# ETH_M_V1.net
KiCad netlist of a schematic drawn in Altium Designer
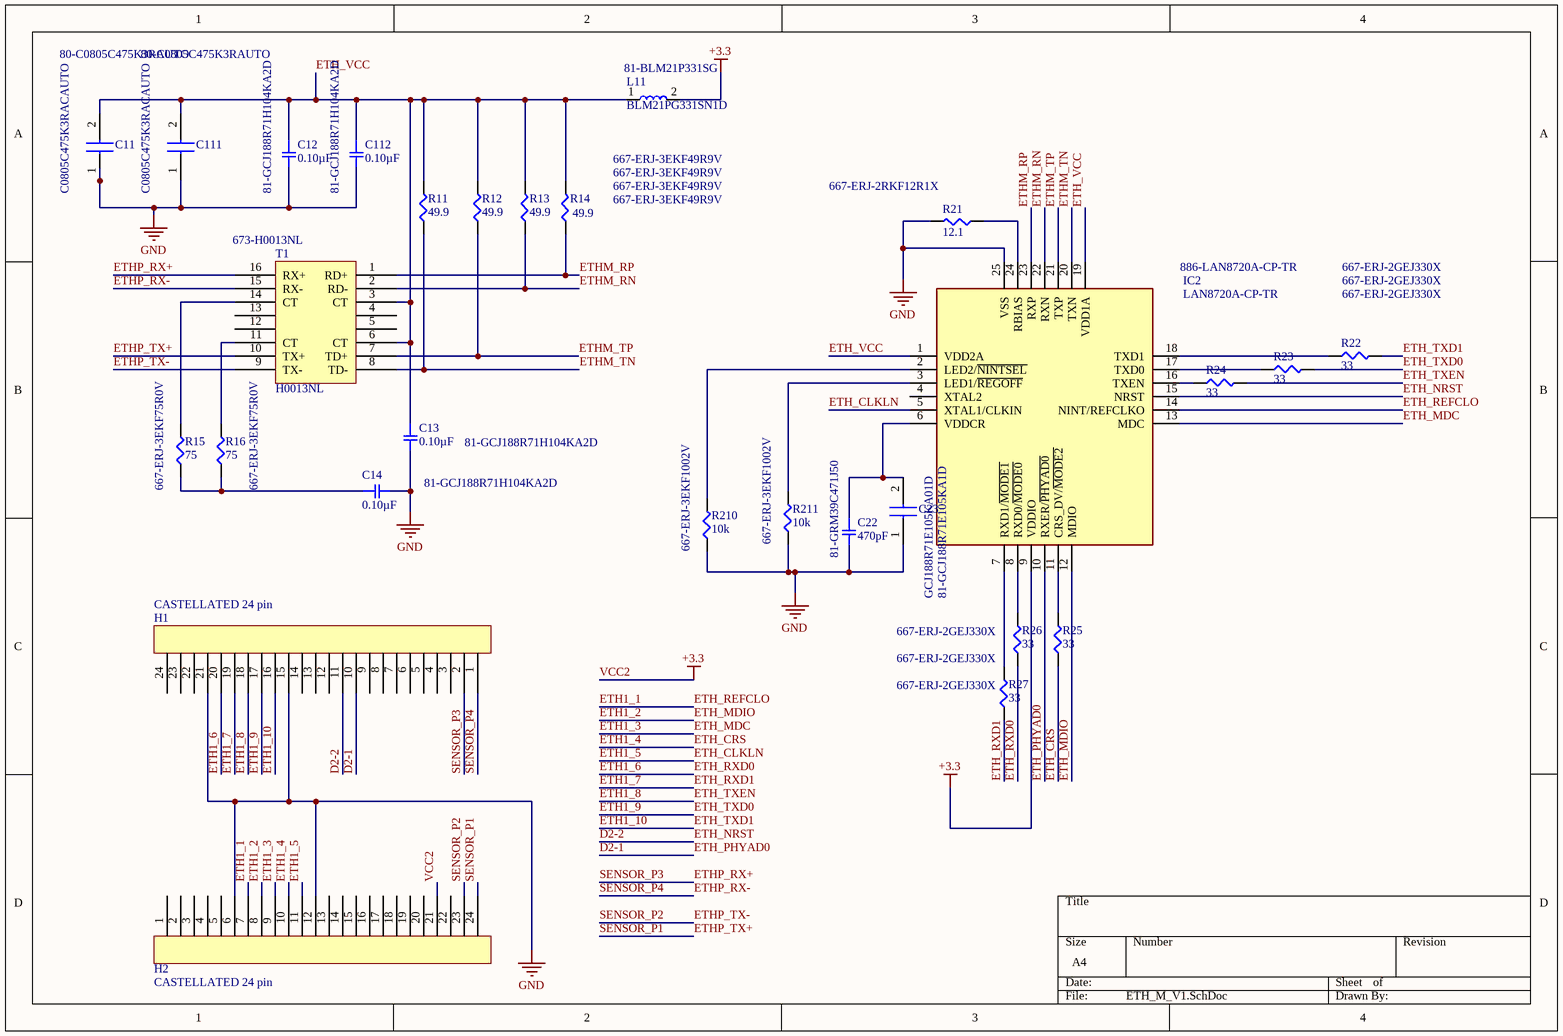
[diagram p0: ETH_M_V1.SchDoc]

(export (version "E")
  (design (tool "Eeschema 10.0.6"))
  (components
    (comp (ref "C11")
      (value "C0805C475K3RACAUTO")
      (footprint "SamacSys:CAPC2012X125N")
      (description "Capacitor")
      (fields
        (field (name "MOUSER2 PART NUMBER") "80-C0805C475K3RAUTO")
        (field (name "SUPPLIER PART NUMBER 1") "80-C0805C475K3RAUTO")
      )
      (libsource (lib "*") (part "C0805C475K3RACAUTO"))
    )
    (comp (ref "C12")
      (value "0.10µF")
      (footprint "SMD-0603C")
      (description "CAP CER 0.1UF 50V X7R 0603")
      (fields
        (field (name "DIGI-KEY PART NUMBER") "490-5798-1-ND")
        (field (name "PART NUMBER") "GCJ188R71H104KA12D")
        (field (name "SUPPLIER PART NUMBER 1") "81-GCJ188R71H104KA2D")
      )
      (libsource (lib "capacitor_murata_0603") (part "GCJ188R71H104KA12D"))
    )
    (comp (ref "C13")
      (value "0.10µF")
      (footprint "SMD-0603C")
      (description "CAP CER 0.1UF 50V X7R 0603")
      (fields
        (field (name "DIGI-KEY PART NUMBER") "490-5798-1-ND")
        (field (name "PART NUMBER") "GCJ188R71H104KA12D")
        (field (name "SUPPLIER PART NUMBER 1") "81-GCJ188R71H104KA2D")
      )
      (libsource (lib "capacitor_murata_0603") (part "GCJ188R71H104KA12D"))
    )
    (comp (ref "C14")
      (value "0.10µF")
      (footprint "SMD-0603C")
      (description "CAP CER 0.1UF 50V X7R 0603")
      (fields
        (field (name "DIGI-KEY PART NUMBER") "490-5798-1-ND")
        (field (name "PART NUMBER") "GCJ188R71H104KA12D")
        (field (name "SUPPLIER PART NUMBER 1") "81-GCJ188R71H104KA2D")
      )
      (libsource (lib "capacitor_murata_0603") (part "GCJ188R71H104KA12D"))
    )
    (comp (ref "C22")
      (value "470pF")
      (footprint "SMD-0603C")
      (description "CAP CER 470PF 50V NP0 0603")
      (fields
        (field (name "DIGI-KEY PART NUMBER") "490-1443-1-ND")
        (field (name "PART NUMBER") "GRM1885C1H471JA01D")
        (field (name "SUPPLIER PART NUMBER 1") "81-GRM39C471J50")
      )
      (libsource (lib "capacitor_murata_0603") (part "GRM1885C1H471JA01D"))
    )
    (comp (ref "C23")
      (value "GCJ188R71E105KA01D")
      (footprint "SamacSys:CAPC1608X100N")
      (description "Capacitor")
      (fields (field (name "SUPPLIER PART NUMBER 1") "81-GCJ188R71E105KA1D"))
      (libsource (lib "*") (part "GCJ188R71E105KA01D"))
    )
    (comp (ref "C111")
      (value "C0805C475K3RACAUTO")
      (footprint "SamacSys:CAPC2012X125N")
      (description "Capacitor")
      (fields
        (field (name "MOUSER2 PART NUMBER") "80-C0805C475K3RAUTO")
        (field (name "SUPPLIER PART NUMBER 1") "80-C0805C475K3RAUTO")
      )
      (libsource (lib "*") (part "C0805C475K3RACAUTO"))
    )
    (comp (ref "C112")
      (value "0.10µF")
      (footprint "SMD-0603C")
      (description "CAP CER 0.1UF 50V X7R 0603")
      (fields
        (field (name "DIGI-KEY PART NUMBER") "490-5798-1-ND")
        (field (name "PART NUMBER") "GCJ188R71H104KA12D")
        (field (name "SUPPLIER PART NUMBER 1") "81-GCJ188R71H104KA2D")
      )
      (libsource (lib "capacitor_murata_0603") (part "GCJ188R71H104KA12D"))
    )
    (comp (ref "H1")
      (value "CASTELLATED 24 pin")
      (footprint "CASTELLATED 24 pin")
      (libsource (lib "") (part "CASTELLATED 24 pin_1"))
    )
    (comp (ref "H2")
      (value "CASTELLATED 24 pin")
      (footprint "CASTELLATED 24 pin")
      (libsource (lib "USIB") (part "CASTELLATED 24 pin"))
    )
    (comp (ref "IC2")
      (value "LAN8720A-CP-TR")
      (footprint "SamacSys:QFN50P400X400X100-25N-D")
      (description "Integrated Circuit")
      (fields
        (field (name "MOUSER2 PART NUMBER") "886-LAN8720A-CP-TR")
        (field (name "SUPPLIER PART NUMBER 1") "886-LAN8720A-CP-TR")
      )
      (libsource (lib "*") (part "LAN8720A-CP-TR"))
    )
    (comp (ref "L11")
      (value "BLM21PG331SN1D")
      (footprint "INDC2012X87")
      (description "Ferrite Beads Multi-Layer 330Ohm 25% 100MHz 1.5A 70mOhm DCR 0805 Paper T/R")
      (fields
        (field (name "MF") "Murata")
        (field (name "DIGI-KEY_PART_NUMBER") "490-5988-1-ND")
        (field (name "SUPPLIER PART NUMBER 1") "81-BLM21P331SG")
      )
      (libsource (lib "BLM21PG331SN1D") (part "BLM21PG331SN1D"))
    )
    (comp (ref "R11")
      (value "49.9")
      (footprint "SMD-0603-RES")
      (description "RES SMD 49.9 OHM 1% 1/10W 0603")
      (fields
        (field (name "PART NUMBER") "ERJ-3EKF49R9V")
        (field (name "DIGI-KEY PART NUMBER") "P49.9HCT-ND")
        (field (name "SUPPLIER PART NUMBER 1") "667-ERJ-3EKF49R9V")
      )
      (libsource (lib "Panasonic_ERJ_0603") (part "ERJ-3EKF49R9V"))
    )
    (comp (ref "R12")
      (value "49.9")
      (footprint "SMD-0603-RES")
      (description "RES SMD 49.9 OHM 1% 1/10W 0603")
      (fields
        (field (name "PART NUMBER") "ERJ-3EKF49R9V")
        (field (name "DIGI-KEY PART NUMBER") "P49.9HCT-ND")
        (field (name "SUPPLIER PART NUMBER 1") "667-ERJ-3EKF49R9V")
      )
      (libsource (lib "Panasonic_ERJ_0603") (part "ERJ-3EKF49R9V"))
    )
    (comp (ref "R13")
      (value "49.9")
      (footprint "SMD-0603-RES")
      (description "RES SMD 49.9 OHM 1% 1/10W 0603")
      (fields
        (field (name "PART NUMBER") "ERJ-3EKF49R9V")
        (field (name "DIGI-KEY PART NUMBER") "P49.9HCT-ND")
        (field (name "SUPPLIER PART NUMBER 1") "667-ERJ-3EKF49R9V")
      )
      (libsource (lib "Panasonic_ERJ_0603") (part "ERJ-3EKF49R9V"))
    )
    (comp (ref "R14")
      (value "49.9")
      (footprint "SMD-0603-RES")
      (description "RES SMD 49.9 OHM 1% 1/10W 0603")
      (fields
        (field (name "PART NUMBER") "ERJ-3EKF49R9V")
        (field (name "DIGI-KEY PART NUMBER") "P49.9HCT-ND")
        (field (name "SUPPLIER PART NUMBER 1") "667-ERJ-3EKF49R9V")
      )
      (libsource (lib "Panasonic_ERJ_0603") (part "ERJ-3EKF49R9V"))
    )
    (comp (ref "R15")
      (value "75")
      (footprint "SMD-0603-RES")
      (description "RES SMD 75 OHM 1% 1/10W 0603")
      (fields
        (field (name "PART NUMBER") "ERJ-3EKF75R0V")
        (field (name "DIGI-KEY PART NUMBER") "P75.0HCT-ND")
        (field (name "SUPPLIER PART NUMBER 1") "667-ERJ-3EKF75R0V")
      )
      (libsource (lib "Panasonic_ERJ_0603") (part "ERJ-3EKF75R0V"))
    )
    (comp (ref "R16")
      (value "75")
      (footprint "SMD-0603-RES")
      (description "RES SMD 75 OHM 1% 1/10W 0603")
      (fields
        (field (name "PART NUMBER") "ERJ-3EKF75R0V")
        (field (name "DIGI-KEY PART NUMBER") "P75.0HCT-ND")
        (field (name "SUPPLIER PART NUMBER 1") "667-ERJ-3EKF75R0V")
      )
      (libsource (lib "Panasonic_ERJ_0603") (part "ERJ-3EKF75R0V"))
    )
    (comp (ref "R21")
      (value "12.1")
      (footprint "SMD-0402-RES")
      (description "RES SMD 12.1 OHM 1% 1/10W 0402")
      (fields
        (field (name "PART NUMBER") "ERJ-2RKF12R1X")
        (field (name "DIGI-KEY PART NUMBER") "P12.1LCT-ND")
        (field (name "SUPPLIER PART NUMBER 1") "667-ERJ-2RKF12R1X")
      )
      (libsource (lib "Panasonic_ERJ_0402") (part "ERJ-2RKF12R1X"))
    )
    (comp (ref "R22")
      (value "33")
      (footprint "SMD-0402-RES")
      (description "RES SMD 33 OHM 5% 1/10W 0402")
      (fields
        (field (name "PART NUMBER") "ERJ-2GEJ330X")
        (field (name "DIGI-KEY PART NUMBER") "P33JCT-ND")
        (field (name "SUPPLIER PART NUMBER 1") "667-ERJ-2GEJ330X")
      )
      (libsource (lib "Panasonic_ERJ_0402") (part "ERJ-2GEJ330X"))
    )
    (comp (ref "R23")
      (value "33")
      (footprint "SMD-0402-RES")
      (description "RES SMD 33 OHM 5% 1/10W 0402")
      (fields
        (field (name "PART NUMBER") "ERJ-2GEJ330X")
        (field (name "DIGI-KEY PART NUMBER") "P33JCT-ND")
        (field (name "SUPPLIER PART NUMBER 1") "667-ERJ-2GEJ330X")
      )
      (libsource (lib "Panasonic_ERJ_0402") (part "ERJ-2GEJ330X"))
    )
    (comp (ref "R24")
      (value "33")
      (footprint "SMD-0402-RES")
      (description "RES SMD 33 OHM 5% 1/10W 0402")
      (fields
        (field (name "PART NUMBER") "ERJ-2GEJ330X")
        (field (name "DIGI-KEY PART NUMBER") "P33JCT-ND")
        (field (name "SUPPLIER PART NUMBER 1") "667-ERJ-2GEJ330X")
      )
      (libsource (lib "Panasonic_ERJ_0402") (part "ERJ-2GEJ330X"))
    )
    (comp (ref "R25")
      (value "33")
      (footprint "SMD-0402-RES")
      (description "RES SMD 33 OHM 5% 1/10W 0402")
      (fields
        (field (name "PART NUMBER") "ERJ-2GEJ330X")
        (field (name "DIGI-KEY PART NUMBER") "P33JCT-ND")
        (field (name "SUPPLIER PART NUMBER 1") "667-ERJ-2GEJ330X")
      )
      (libsource (lib "Panasonic_ERJ_0402") (part "ERJ-2GEJ330X"))
    )
    (comp (ref "R26")
      (value "33")
      (footprint "SMD-0402-RES")
      (description "RES SMD 33 OHM 5% 1/10W 0402")
      (fields
        (field (name "PART NUMBER") "ERJ-2GEJ330X")
        (field (name "DIGI-KEY PART NUMBER") "P33JCT-ND")
        (field (name "SUPPLIER PART NUMBER 1") "667-ERJ-2GEJ330X")
      )
      (libsource (lib "Panasonic_ERJ_0402") (part "ERJ-2GEJ330X"))
    )
    (comp (ref "R27")
      (value "33")
      (footprint "SMD-0402-RES")
      (description "RES SMD 33 OHM 5% 1/10W 0402")
      (fields
        (field (name "PART NUMBER") "ERJ-2GEJ330X")
        (field (name "DIGI-KEY PART NUMBER") "P33JCT-ND")
        (field (name "SUPPLIER PART NUMBER 1") "667-ERJ-2GEJ330X")
      )
      (libsource (lib "Panasonic_ERJ_0402") (part "ERJ-2GEJ330X"))
    )
    (comp (ref "R210")
      (value "10k")
      (footprint "SMD-0603-RES")
      (description "RES SMD 10K OHM 1% 1/10W 0603")
      (fields
        (field (name "PART NUMBER") "ERJ-3EKF1002V")
        (field (name "DIGI-KEY PART NUMBER") "P10.0KHCT-ND")
        (field (name "SUPPLIER PART NUMBER 1") "667-ERJ-3EKF1002V")
      )
      (libsource (lib "Panasonic_ERJ_0603") (part "ERJ-3EKF1002V"))
    )
    (comp (ref "R211")
      (value "10k")
      (footprint "SMD-0603-RES")
      (description "RES SMD 10K OHM 1% 1/10W 0603")
      (fields
        (field (name "PART NUMBER") "ERJ-3EKF1002V")
        (field (name "DIGI-KEY PART NUMBER") "P10.0KHCT-ND")
        (field (name "SUPPLIER PART NUMBER 1") "667-ERJ-3EKF1002V")
      )
      (libsource (lib "Panasonic_ERJ_0603") (part "ERJ-3EKF1002V"))
    )
    (comp (ref "T1")
      (value "H0013NL")
      (footprint "SamacSys:H0013NL")
      (description "Transformer")
      (fields (field (name "SUPPLIER PART NUMBER 1") "673-H0013NL"))
      (libsource (lib "SamacSys") (part "H0013NL"))
    )
  )
  (nets
    (net (code "1") (name "+3.3") (class "Default")
      (node (ref "H2") (pin "21") (pintype "passive"))
      (node (ref "IC2") (pin "9") (pinfunction "VDDIO_9") (pintype "passive"))
      (node (ref "L11") (pin "2") (pinfunction "2_2") (pintype "passive"))
    )
    (net (code "2") (name "/D2-1") (class "Default")
      (node (ref "H1") (pin "10") (pintype "passive"))
      (node (ref "IC2") (pin "10") (pinfunction "RXER/~{PHYAD0}_10") (pintype "passive"))
    )
    (net (code "3") (name "/D2-2") (class "Default")
      (node (ref "H1") (pin "11") (pintype "passive"))
      (node (ref "IC2") (pin "15") (pinfunction "NRST_15") (pintype "passive"))
    )
    (net (code "4") (name "/ETH1_1") (class "Default")
      (node (ref "H2") (pin "7") (pintype "passive"))
      (node (ref "IC2") (pin "14") (pinfunction "NINT/REFCLKO_14") (pintype "passive"))
    )
    (net (code "5") (name "/ETH1_2") (class "Default")
      (node (ref "H2") (pin "8") (pintype "passive"))
      (node (ref "IC2") (pin "12") (pinfunction "MDIO_12") (pintype "passive"))
    )
    (net (code "6") (name "/ETH1_3") (class "Default")
      (node (ref "H2") (pin "9") (pintype "passive"))
      (node (ref "IC2") (pin "13") (pinfunction "MDC_13") (pintype "passive"))
    )
    (net (code "7") (name "/ETH1_4") (class "Default")
      (node (ref "H2") (pin "10") (pintype "passive"))
      (node (ref "R25") (pin "1") (pinfunction "1_1") (pintype "passive"))
    )
    (net (code "8") (name "/ETH1_5") (class "Default")
      (node (ref "H2") (pin "11") (pintype "passive"))
      (node (ref "IC2") (pin "5") (pinfunction "XTAL1/CLKIN_5") (pintype "passive"))
    )
    (net (code "9") (name "/ETH1_6") (class "Default")
      (node (ref "H1") (pin "20") (pintype "passive"))
      (node (ref "R26") (pin "1") (pinfunction "1_1") (pintype "passive"))
    )
    (net (code "10") (name "/ETH1_7") (class "Default")
      (node (ref "H1") (pin "19") (pintype "passive"))
      (node (ref "R27") (pin "1") (pinfunction "1_1") (pintype "passive"))
    )
    (net (code "11") (name "/ETH1_8") (class "Default")
      (node (ref "H1") (pin "18") (pintype "passive"))
      (node (ref "R24") (pin "2") (pinfunction "2_2") (pintype "passive"))
    )
    (net (code "12") (name "/ETH1_9") (class "Default")
      (node (ref "H1") (pin "17") (pintype "passive"))
      (node (ref "R23") (pin "2") (pinfunction "2_2") (pintype "passive"))
    )
    (net (code "13") (name "/ETH1_10") (class "Default")
      (node (ref "H1") (pin "16") (pintype "passive"))
      (node (ref "R22") (pin "2") (pinfunction "2_2") (pintype "passive"))
    )
    (net (code "14") (name "/ETHM_RN") (class "Default")
      (node (ref "IC2") (pin "22") (pinfunction "RXN_22") (pintype "passive"))
      (node (ref "R13") (pin "1") (pinfunction "1_1") (pintype "passive"))
      (node (ref "T1") (pin "2") (pinfunction "RD-_2") (pintype "passive"))
    )
    (net (code "15") (name "/ETHM_RP") (class "Default")
      (node (ref "IC2") (pin "23") (pinfunction "RXP_23") (pintype "passive"))
      (node (ref "R14") (pin "1") (pinfunction "1_1") (pintype "passive"))
      (node (ref "T1") (pin "1") (pinfunction "RD+_1") (pintype "passive"))
    )
    (net (code "16") (name "/ETHM_TN") (class "Default")
      (node (ref "IC2") (pin "20") (pinfunction "TXN_20") (pintype "passive"))
      (node (ref "R11") (pin "1") (pinfunction "1_1") (pintype "passive"))
      (node (ref "T1") (pin "8") (pinfunction "TD-_8") (pintype "passive"))
    )
    (net (code "17") (name "/ETHM_TP") (class "Default")
      (node (ref "IC2") (pin "21") (pinfunction "TXP_21") (pintype "passive"))
      (node (ref "R12") (pin "1") (pinfunction "1_1") (pintype "passive"))
      (node (ref "T1") (pin "7") (pinfunction "TD+_7") (pintype "passive"))
    )
    (net (code "18") (name "/ETHP_RX+") (class "Default")
      (node (ref "H1") (pin "2") (pintype "passive"))
      (node (ref "T1") (pin "16") (pinfunction "RX+_16") (pintype "passive"))
    )
    (net (code "19") (name "/ETHP_RX-") (class "Default")
      (node (ref "H1") (pin "1") (pintype "passive"))
      (node (ref "T1") (pin "15") (pinfunction "RX-_15") (pintype "passive"))
    )
    (net (code "20") (name "/ETHP_TX+") (class "Default")
      (node (ref "H2") (pin "24") (pintype "passive"))
      (node (ref "T1") (pin "10") (pinfunction "TX+_10") (pintype "passive"))
    )
    (net (code "21") (name "/ETHP_TX-") (class "Default")
      (node (ref "H2") (pin "23") (pintype "passive"))
      (node (ref "T1") (pin "9") (pinfunction "TX-_9") (pintype "passive"))
    )
    (net (code "22") (name "/ETH_VCC") (class "Default")
      (node (ref "C11") (pin "2") (pinfunction "2_2") (pintype "passive"))
      (node (ref "C111") (pin "2") (pinfunction "2_2") (pintype "passive"))
      (node (ref "C112") (pin "1") (pinfunction "1_1") (pintype "passive"))
      (node (ref "C12") (pin "1") (pinfunction "1_1") (pintype "passive"))
      (node (ref "C13") (pin "1") (pinfunction "1_1") (pintype "passive"))
      (node (ref "IC2") (pin "1") (pinfunction "VDD2A_1") (pintype "passive"))
      (node (ref "IC2") (pin "19") (pinfunction "VDD1A_19") (pintype "passive"))
      (node (ref "L11") (pin "1") (pinfunction "1_1") (pintype "passive"))
      (node (ref "R11") (pin "2") (pinfunction "2_2") (pintype "passive"))
      (node (ref "R12") (pin "2") (pinfunction "2_2") (pintype "passive"))
      (node (ref "R13") (pin "2") (pinfunction "2_2") (pintype "passive"))
      (node (ref "R14") (pin "2") (pinfunction "2_2") (pintype "passive"))
      (node (ref "T1") (pin "3") (pinfunction "CT_3") (pintype "passive"))
      (node (ref "T1") (pin "6") (pinfunction "CT_6") (pintype "passive"))
    )
    (net (code "23") (name "GND") (class "Default")
      (node (ref "C11") (pin "1") (pinfunction "1_1") (pintype "passive"))
      (node (ref "C111") (pin "1") (pinfunction "1_1") (pintype "passive"))
      (node (ref "C112") (pin "2") (pinfunction "2_2") (pintype "passive"))
      (node (ref "C12") (pin "2") (pinfunction "2_2") (pintype "passive"))
      (node (ref "C13") (pin "2") (pinfunction "2_2") (pintype "passive"))
      (node (ref "C14") (pin "2") (pinfunction "2_2") (pintype "passive"))
      (node (ref "C22") (pin "2") (pinfunction "2_2") (pintype "passive"))
      (node (ref "C23") (pin "1") (pinfunction "1_1") (pintype "passive"))
      (node (ref "H1") (pin "15") (pintype "passive"))
      (node (ref "H1") (pin "21") (pintype "passive"))
      (node (ref "H2") (pin "12") (pintype "passive"))
      (node (ref "H2") (pin "6") (pintype "passive"))
      (node (ref "IC2") (pin "25") (pinfunction "VSS_25") (pintype "passive"))
      (node (ref "R21") (pin "2") (pinfunction "2_2") (pintype "passive"))
      (node (ref "R210") (pin "1") (pinfunction "1_1") (pintype "passive"))
      (node (ref "R211") (pin "1") (pinfunction "1_1") (pintype "passive"))
    )
    (net (code "24") (name "Net-(C14-Pad1)") (class "Default")
      (node (ref "C14") (pin "1") (pinfunction "1_1") (pintype "passive"))
      (node (ref "R15") (pin "1") (pinfunction "1_1") (pintype "passive"))
      (node (ref "R16") (pin "1") (pinfunction "1_1") (pintype "passive"))
    )
    (net (code "25") (name "Net-(IC2-CRS_DV{slash}~{MODE2})") (class "Default")
      (node (ref "IC2") (pin "11") (pinfunction "CRS_DV/~{MODE2}_11") (pintype "passive"))
      (node (ref "R25") (pin "2") (pinfunction "2_2") (pintype "passive"))
    )
    (net (code "26") (name "Net-(IC2-LED1{slash}~{REGOFF})") (class "Default")
      (node (ref "IC2") (pin "3") (pinfunction "LED1/~{REGOFF}_3") (pintype "passive"))
      (node (ref "R211") (pin "2") (pinfunction "2_2") (pintype "passive"))
    )
    (net (code "27") (name "Net-(IC2-LED2{slash}~{NINTSEL})") (class "Default")
      (node (ref "IC2") (pin "2") (pinfunction "LED2/~{NINTSEL}_2") (pintype "passive"))
      (node (ref "R210") (pin "2") (pinfunction "2_2") (pintype "passive"))
    )
    (net (code "28") (name "Net-(IC2-RBIAS)") (class "Default")
      (node (ref "IC2") (pin "24") (pinfunction "RBIAS_24") (pintype "passive"))
      (node (ref "R21") (pin "1") (pinfunction "1_1") (pintype "passive"))
    )
    (net (code "29") (name "Net-(IC2-RXD0{slash}~{MODE0})") (class "Default")
      (node (ref "IC2") (pin "8") (pinfunction "RXD0/~{MODE0}_8") (pintype "passive"))
      (node (ref "R26") (pin "2") (pinfunction "2_2") (pintype "passive"))
    )
    (net (code "30") (name "Net-(IC2-RXD1{slash}~{MODE1})") (class "Default")
      (node (ref "IC2") (pin "7") (pinfunction "RXD1/~{MODE1}_7") (pintype "passive"))
      (node (ref "R27") (pin "2") (pinfunction "2_2") (pintype "passive"))
    )
    (net (code "31") (name "Net-(IC2-TXD0)") (class "Default")
      (node (ref "IC2") (pin "17") (pinfunction "TXD0_17") (pintype "passive"))
      (node (ref "R23") (pin "1") (pinfunction "1_1") (pintype "passive"))
    )
    (net (code "32") (name "Net-(IC2-TXD1)") (class "Default")
      (node (ref "IC2") (pin "18") (pinfunction "TXD1_18") (pintype "passive"))
      (node (ref "R22") (pin "1") (pinfunction "1_1") (pintype "passive"))
    )
    (net (code "33") (name "Net-(IC2-TXEN)") (class "Default")
      (node (ref "IC2") (pin "16") (pinfunction "TXEN_16") (pintype "passive"))
      (node (ref "R24") (pin "1") (pinfunction "1_1") (pintype "passive"))
    )
    (net (code "34") (name "Net-(IC2-VDDCR)") (class "Default")
      (node (ref "C22") (pin "1") (pinfunction "1_1") (pintype "passive"))
      (node (ref "C23") (pin "2") (pinfunction "2_2") (pintype "passive"))
      (node (ref "IC2") (pin "6") (pinfunction "VDDCR_6") (pintype "passive"))
    )
    (net (code "35") (name "Net-(R15-Pad2)") (class "Default")
      (node (ref "R15") (pin "2") (pinfunction "2_2") (pintype "passive"))
      (node (ref "T1") (pin "14") (pinfunction "CT_14") (pintype "passive"))
    )
    (net (code "36") (name "Net-(R16-Pad2)") (class "Default")
      (node (ref "R16") (pin "2") (pinfunction "2_2") (pintype "passive"))
      (node (ref "T1") (pin "11") (pinfunction "CT_11") (pintype "passive"))
    )
    (net (code "37") (name "unconnected-(H1-Pad3)") (class "Default")
      (node (ref "H1") (pin "3") (pintype "passive"))
    )
    (net (code "38") (name "unconnected-(H1-Pad4)") (class "Default")
      (node (ref "H1") (pin "4") (pintype "passive"))
    )
    (net (code "39") (name "unconnected-(H1-Pad5)") (class "Default")
      (node (ref "H1") (pin "5") (pintype "passive"))
    )
    (net (code "40") (name "unconnected-(H1-Pad6)") (class "Default")
      (node (ref "H1") (pin "6") (pintype "passive"))
    )
    (net (code "41") (name "unconnected-(H1-Pad7)") (class "Default")
      (node (ref "H1") (pin "7") (pintype "passive"))
    )
    (net (code "42") (name "unconnected-(H1-Pad8)") (class "Default")
      (node (ref "H1") (pin "8") (pintype "passive"))
    )
    (net (code "43") (name "unconnected-(H1-Pad9)") (class "Default")
      (node (ref "H1") (pin "9") (pintype "passive"))
    )
    (net (code "44") (name "unconnected-(H1-Pad12)") (class "Default")
      (node (ref "H1") (pin "12") (pintype "passive"))
    )
    (net (code "45") (name "unconnected-(H1-Pad13)") (class "Default")
      (node (ref "H1") (pin "13") (pintype "passive"))
    )
    (net (code "46") (name "unconnected-(H1-Pad14)") (class "Default")
      (node (ref "H1") (pin "14") (pintype "passive"))
    )
    (net (code "47") (name "unconnected-(H1-Pad22)") (class "Default")
      (node (ref "H1") (pin "22") (pintype "passive"))
    )
    (net (code "48") (name "unconnected-(H1-Pad23)") (class "Default")
      (node (ref "H1") (pin "23") (pintype "passive"))
    )
    (net (code "49") (name "unconnected-(H1-Pad24)") (class "Default")
      (node (ref "H1") (pin "24") (pintype "passive"))
    )
    (net (code "50") (name "unconnected-(H2-Pad1)") (class "Default")
      (node (ref "H2") (pin "1") (pintype "passive"))
    )
    (net (code "51") (name "unconnected-(H2-Pad2)") (class "Default")
      (node (ref "H2") (pin "2") (pintype "passive"))
    )
    (net (code "52") (name "unconnected-(H2-Pad3)") (class "Default")
      (node (ref "H2") (pin "3") (pintype "passive"))
    )
    (net (code "53") (name "unconnected-(H2-Pad4)") (class "Default")
      (node (ref "H2") (pin "4") (pintype "passive"))
    )
    (net (code "54") (name "unconnected-(H2-Pad5)") (class "Default")
      (node (ref "H2") (pin "5") (pintype "passive"))
    )
    (net (code "55") (name "unconnected-(H2-Pad13)") (class "Default")
      (node (ref "H2") (pin "13") (pintype "passive"))
    )
    (net (code "56") (name "unconnected-(H2-Pad14)") (class "Default")
      (node (ref "H2") (pin "14") (pintype "passive"))
    )
    (net (code "57") (name "unconnected-(H2-Pad15)") (class "Default")
      (node (ref "H2") (pin "15") (pintype "passive"))
    )
    (net (code "58") (name "unconnected-(H2-Pad16)") (class "Default")
      (node (ref "H2") (pin "16") (pintype "passive"))
    )
    (net (code "59") (name "unconnected-(H2-Pad17)") (class "Default")
      (node (ref "H2") (pin "17") (pintype "passive"))
    )
    (net (code "60") (name "unconnected-(H2-Pad18)") (class "Default")
      (node (ref "H2") (pin "18") (pintype "passive"))
    )
    (net (code "61") (name "unconnected-(H2-Pad19)") (class "Default")
      (node (ref "H2") (pin "19") (pintype "passive"))
    )
    (net (code "62") (name "unconnected-(H2-Pad20)") (class "Default")
      (node (ref "H2") (pin "20") (pintype "passive"))
    )
    (net (code "63") (name "unconnected-(H2-Pad22)") (class "Default")
      (node (ref "H2") (pin "22") (pintype "passive"))
    )
    (net (code "64") (name "unconnected-(IC2-XTAL2-Pad4)") (class "Default")
      (node (ref "IC2") (pin "4") (pinfunction "XTAL2_4") (pintype "passive"))
    )
    (net (code "65") (name "unconnected-(T1-Pad4)") (class "Default")
      (node (ref "T1") (pin "4") (pintype "passive"))
    )
    (net (code "66") (name "unconnected-(T1-Pad5)") (class "Default")
      (node (ref "T1") (pin "5") (pintype "passive"))
    )
    (net (code "67") (name "unconnected-(T1-Pad12)") (class "Default")
      (node (ref "T1") (pin "12") (pintype "passive"))
    )
    (net (code "68") (name "unconnected-(T1-Pad13)") (class "Default")
      (node (ref "T1") (pin "13") (pintype "passive"))
    )
  )
)
